# Usbasp_Pdi.net
KiCad netlist of a schematic drawn in EAGLE
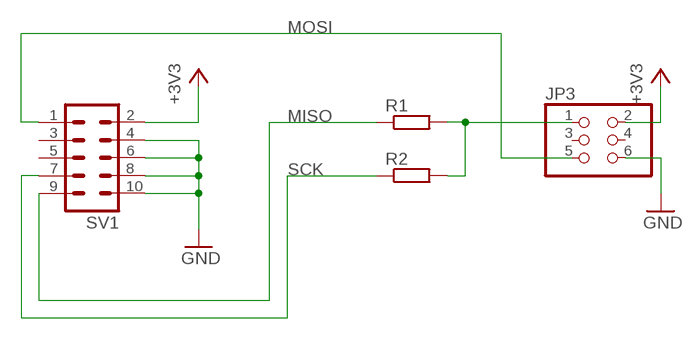
[diagram p0: schematic, sheet 1]

(export (version "E")
  (design (tool "Eeschema 10.0.6"))
  (components
    (comp (ref "JP3")
      (value "PINHD-2X03_2.54")
      (footprint "eagle-import:2X03")
      (libsource (lib "eagle-import") (part "PINHD-2X03_2.54"))
    )
    (comp (ref "R1")
      (value "R-EU_R0603")
      (footprint "eagle-import:R0603")
      (libsource (lib "eagle-import") (part "R-EU_R0603"))
    )
    (comp (ref "R2")
      (value "R-EU_R0603")
      (footprint "eagle-import:R0603")
      (libsource (lib "eagle-import") (part "R-EU_R0603"))
    )
    (comp (ref "SV1")
      (value "ML10")
      (footprint "eagle-import:ML10")
      (libsource (lib "eagle-import") (part "ML10"))
    )
  )
  (nets
    (net (code "1") (name "+3V3") (class "Default")
      (node (ref "JP3") (pin "2") (pinfunction "2_2") (pintype "passive"))
      (node (ref "SV1") (pin "2") (pinfunction "2_2") (pintype "passive"))
    )
    (net (code "2") (name "/MISO") (class "Default")
      (node (ref "R1") (pin "1") (pinfunction "1_1") (pintype "passive"))
      (node (ref "SV1") (pin "9") (pinfunction "9_9") (pintype "passive"))
    )
    (net (code "3") (name "/MOSI") (class "Default")
      (node (ref "JP3") (pin "5") (pinfunction "5_5") (pintype "passive"))
      (node (ref "SV1") (pin "1") (pinfunction "1_1") (pintype "passive"))
    )
    (net (code "4") (name "/SCK") (class "Default")
      (node (ref "R2") (pin "1") (pinfunction "1_1") (pintype "passive"))
      (node (ref "SV1") (pin "7") (pinfunction "7_7") (pintype "passive"))
    )
    (net (code "5") (name "GND") (class "Default")
      (node (ref "JP3") (pin "6") (pinfunction "6_6") (pintype "passive"))
      (node (ref "SV1") (pin "10") (pinfunction "10_10") (pintype "passive"))
      (node (ref "SV1") (pin "4") (pinfunction "4_4") (pintype "passive"))
      (node (ref "SV1") (pin "6") (pinfunction "6_6") (pintype "passive"))
      (node (ref "SV1") (pin "8") (pinfunction "8_8") (pintype "passive"))
    )
    (net (code "6") (name "Net-(JP3-Pad1)") (class "Default")
      (node (ref "JP3") (pin "1") (pinfunction "1_1") (pintype "passive"))
      (node (ref "R1") (pin "2") (pinfunction "2_2") (pintype "passive"))
      (node (ref "R2") (pin "2") (pinfunction "2_2") (pintype "passive"))
    )
    (net (code "7") (name "unconnected-(JP3-Pad3)") (class "Default")
      (node (ref "JP3") (pin "3") (pinfunction "3_3") (pintype "passive"))
    )
    (net (code "8") (name "unconnected-(JP3-Pad4)") (class "Default")
      (node (ref "JP3") (pin "4") (pinfunction "4_4") (pintype "passive"))
    )
    (net (code "9") (name "unconnected-(SV1-Pad3)") (class "Default")
      (node (ref "SV1") (pin "3") (pinfunction "3_3") (pintype "passive"))
    )
    (net (code "10") (name "unconnected-(SV1-Pad5)") (class "Default")
      (node (ref "SV1") (pin "5") (pinfunction "5_5") (pintype "passive"))
    )
  )
)
